# etna-main-ui.net
KiCad netlist of a schematic drawn in Altium Designer
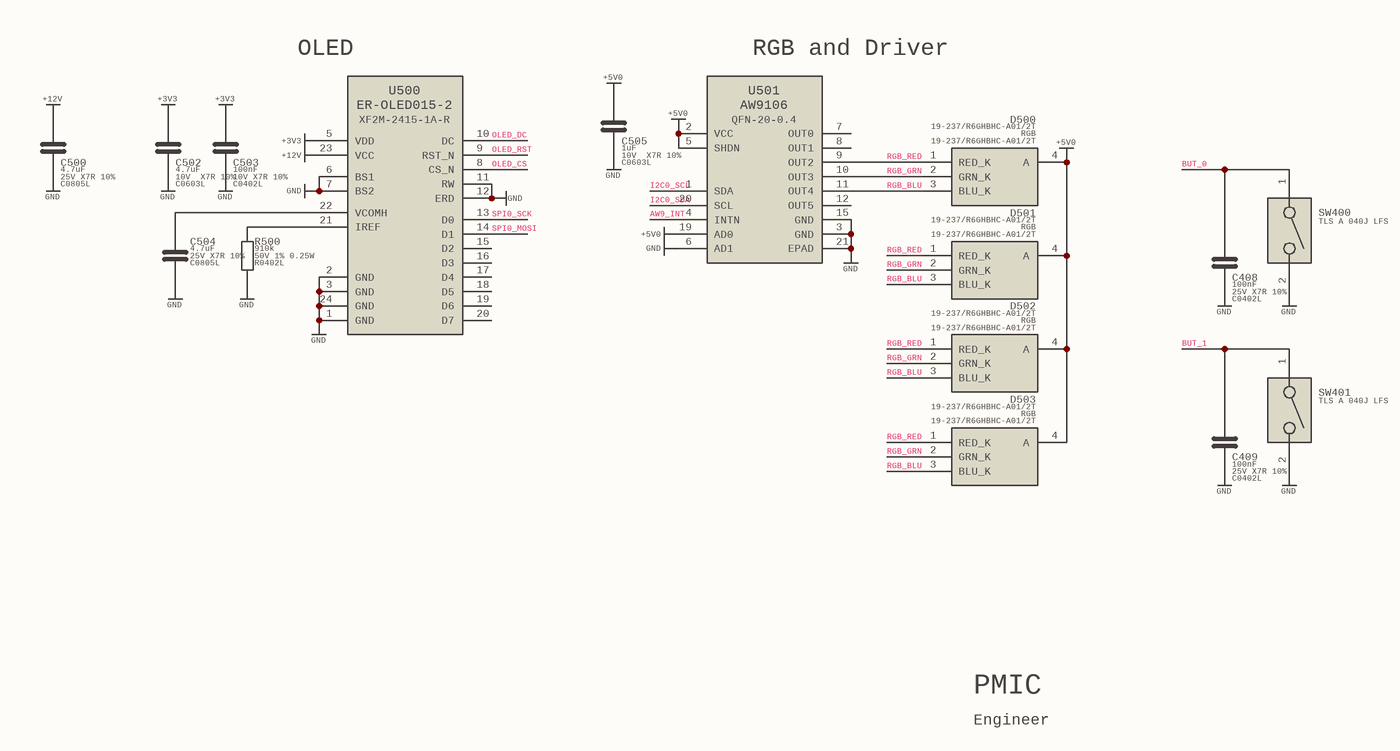
[diagram p0: etna-main-ui.SchDoc]

(export (version "E")
  (design (tool "Eeschema 10.0.6"))
  (components
    (comp (ref "C408")
      (value "100nF")
      (footprint "C0402L")
      (fields (field (name "SPECIFICATION") "25V X7R 10%"))
      (libsource (lib "passive") (part "CAPACITOR_NONPOL"))
    )
    (comp (ref "C409")
      (value "100nF")
      (footprint "C0402L")
      (fields (field (name "SPECIFICATION") "25V X7R 10%"))
      (libsource (lib "passive") (part "CAPACITOR_NONPOL"))
    )
    (comp (ref "C500")
      (value "4.7uF")
      (footprint "C0805L")
      (fields (field (name "SPECIFICATION") "25V X7R 10%"))
      (libsource (lib "passive") (part "CAPACITOR_NONPOL"))
    )
    (comp (ref "C502")
      (value "4.7uF")
      (footprint "C0603L")
      (fields (field (name "SPECIFICATION") "10V  X7R 10%"))
      (libsource (lib "passive") (part "CAPACITOR_NONPOL"))
    )
    (comp (ref "C503")
      (value "100nF")
      (footprint "C0402L")
      (fields (field (name "SPECIFICATION") "10V X7R 10%"))
      (libsource (lib "passive") (part "CAPACITOR_NONPOL"))
    )
    (comp (ref "C504")
      (value "4.7uF")
      (footprint "C0805L")
      (fields (field (name "SPECIFICATION") "25V X7R 10%"))
      (libsource (lib "passive") (part "CAPACITOR_NONPOL"))
    )
    (comp (ref "C505")
      (value "1uF")
      (footprint "C0603L")
      (fields (field (name "SPECIFICATION") "10V  X7R 10%"))
      (libsource (lib "passive") (part "CAPACITOR_NONPOL"))
    )
    (comp (ref "D500")
      (value "19-237/R6GHBHC-A01/2T")
      (footprint "19-237/R6GHBHC-A01/2T")
      (fields (field (name "SPECIFICATION") "RGB"))
      (libsource (lib "discreet") (part "19-237/R6GHBHC-A01/2T"))
    )
    (comp (ref "D501")
      (value "19-237/R6GHBHC-A01/2T")
      (footprint "19-237/R6GHBHC-A01/2T")
      (fields (field (name "SPECIFICATION") "RGB"))
      (libsource (lib "discreet") (part "19-237/R6GHBHC-A01/2T"))
    )
    (comp (ref "D502")
      (value "19-237/R6GHBHC-A01/2T")
      (footprint "19-237/R6GHBHC-A01/2T")
      (fields (field (name "SPECIFICATION") "RGB"))
      (libsource (lib "discreet") (part "19-237/R6GHBHC-A01/2T"))
    )
    (comp (ref "D503")
      (value "19-237/R6GHBHC-A01/2T")
      (footprint "19-237/R6GHBHC-A01/2T")
      (fields (field (name "SPECIFICATION") "RGB"))
      (libsource (lib "discreet") (part "19-237/R6GHBHC-A01/2T"))
    )
    (comp (ref "R500")
      (value "910k")
      (footprint "R0402L")
      (fields (field (name "SPECIFICATION") "50V 1% 0.25W"))
      (libsource (lib "passive") (part "RESISTOR"))
    )
    (comp (ref "SW400")
      (value "TLS A 040J LFS")
      (footprint "TLS A 040J LFS")
      (libsource (lib "legacy") (part "SWITCH"))
    )
    (comp (ref "SW401")
      (value "TLS A 040J LFS")
      (footprint "TLS A 040J LFS")
      (libsource (lib "legacy") (part "SWITCH"))
    )
    (comp (ref "U500")
      (value "ER-OLED015-2")
      (footprint "XF2M-2415-1A-R")
      (libsource (lib "ic") (part "ER-OLED015-2"))
    )
    (comp (ref "U501")
      (value "AW9106")
      (footprint "QFN-20-0.4")
      (fields (field (name "Comment") "AW9109"))
      (libsource (lib "ic") (part "AW9106"))
    )
  )
  (nets
    (net (code "1") (name "+3V3") (class "Default")
      (node (ref "C502") (pin "1") (pinfunction "1_1") (pintype "passive"))
      (node (ref "C503") (pin "1") (pinfunction "1_1") (pintype "passive"))
      (node (ref "U500") (pin "5") (pinfunction "VDD_5") (pintype "passive"))
    )
    (net (code "2") (name "+5V0") (class "Default")
      (node (ref "C505") (pin "1") (pinfunction "1_1") (pintype "passive"))
      (node (ref "D500") (pin "4") (pinfunction "A_4") (pintype "passive"))
      (node (ref "D501") (pin "4") (pinfunction "A_4") (pintype "passive"))
      (node (ref "D502") (pin "4") (pinfunction "A_4") (pintype "passive"))
      (node (ref "D503") (pin "4") (pinfunction "A_4") (pintype "passive"))
      (node (ref "U501") (pin "19") (pinfunction "AD0_19") (pintype "passive"))
      (node (ref "U501") (pin "2") (pinfunction "VCC_2") (pintype "passive"))
      (node (ref "U501") (pin "5") (pinfunction "SHDN_5") (pintype "passive"))
    )
    (net (code "3") (name "+12V") (class "Default")
      (node (ref "C500") (pin "1") (pinfunction "1_1") (pintype "passive"))
      (node (ref "U500") (pin "23") (pinfunction "VCC_23") (pintype "passive"))
    )
    (net (code "4") (name "/AW9_INT") (class "Default")
      (node (ref "U501") (pin "4") (pinfunction "INTN_4") (pintype "passive"))
    )
    (net (code "5") (name "/BUT_0") (class "Default")
      (node (ref "C408") (pin "1") (pinfunction "1_1") (pintype "passive"))
      (node (ref "SW400") (pin "1") (pinfunction "1_1") (pintype "passive"))
    )
    (net (code "6") (name "/BUT_1") (class "Default")
      (node (ref "C409") (pin "1") (pinfunction "1_1") (pintype "passive"))
      (node (ref "SW401") (pin "1") (pinfunction "1_1") (pintype "passive"))
    )
    (net (code "7") (name "/I2C0_SCL") (class "Default")
      (node (ref "U501") (pin "1") (pinfunction "SDA_1") (pintype "passive"))
    )
    (net (code "8") (name "/I2C0_SDA") (class "Default")
      (node (ref "U501") (pin "20") (pinfunction "SCL_20") (pintype "passive"))
    )
    (net (code "9") (name "/OLED_CS") (class "Default")
      (node (ref "U500") (pin "8") (pinfunction "CS_N_8") (pintype "passive"))
    )
    (net (code "10") (name "/OLED_DC") (class "Default")
      (node (ref "U500") (pin "10") (pinfunction "DC_10") (pintype "passive"))
    )
    (net (code "11") (name "/OLED_RST") (class "Default")
      (node (ref "U500") (pin "9") (pinfunction "RST_N_9") (pintype "passive"))
    )
    (net (code "12") (name "/RGB_BLU") (class "Default")
      (node (ref "D500") (pin "3") (pinfunction "BLU_K_3") (pintype "passive"))
      (node (ref "D501") (pin "3") (pinfunction "BLU_K_3") (pintype "passive"))
      (node (ref "D502") (pin "3") (pinfunction "BLU_K_3") (pintype "passive"))
      (node (ref "D503") (pin "3") (pinfunction "BLU_K_3") (pintype "passive"))
      (node (ref "U501") (pin "11") (pinfunction "OUT4_11") (pintype "passive"))
    )
    (net (code "13") (name "/RGB_GRN") (class "Default")
      (node (ref "D500") (pin "2") (pinfunction "GRN_K_2") (pintype "passive"))
      (node (ref "D501") (pin "2") (pinfunction "GRN_K_2") (pintype "passive"))
      (node (ref "D502") (pin "2") (pinfunction "GRN_K_2") (pintype "passive"))
      (node (ref "D503") (pin "2") (pinfunction "GRN_K_2") (pintype "passive"))
      (node (ref "U501") (pin "10") (pinfunction "OUT3_10") (pintype "passive"))
    )
    (net (code "14") (name "/RGB_RED") (class "Default")
      (node (ref "D500") (pin "1") (pinfunction "RED_K_1") (pintype "passive"))
      (node (ref "D501") (pin "1") (pinfunction "RED_K_1") (pintype "passive"))
      (node (ref "D502") (pin "1") (pinfunction "RED_K_1") (pintype "passive"))
      (node (ref "D503") (pin "1") (pinfunction "RED_K_1") (pintype "passive"))
      (node (ref "U501") (pin "9") (pinfunction "OUT2_9") (pintype "passive"))
    )
    (net (code "15") (name "/SPI0_MOSI") (class "Default")
      (node (ref "U500") (pin "14") (pinfunction "D1_14") (pintype "passive"))
    )
    (net (code "16") (name "/SPI0_SCK") (class "Default")
      (node (ref "U500") (pin "13") (pinfunction "D0_13") (pintype "passive"))
    )
    (net (code "17") (name "GND") (class "Default")
      (node (ref "C408") (pin "2") (pinfunction "2_2") (pintype "passive"))
      (node (ref "C409") (pin "2") (pinfunction "2_2") (pintype "passive"))
      (node (ref "C500") (pin "2") (pinfunction "2_2") (pintype "passive"))
      (node (ref "C502") (pin "2") (pinfunction "2_2") (pintype "passive"))
      (node (ref "C503") (pin "2") (pinfunction "2_2") (pintype "passive"))
      (node (ref "C504") (pin "2") (pinfunction "2_2") (pintype "passive"))
      (node (ref "C505") (pin "2") (pinfunction "2_2") (pintype "passive"))
      (node (ref "R500") (pin "2") (pinfunction "2_2") (pintype "passive"))
      (node (ref "SW400") (pin "2") (pinfunction "2_2") (pintype "passive"))
      (node (ref "SW401") (pin "2") (pinfunction "2_2") (pintype "passive"))
      (node (ref "U500") (pin "1") (pinfunction "GND_1") (pintype "passive"))
      (node (ref "U500") (pin "11") (pinfunction "RW_11") (pintype "passive"))
      (node (ref "U500") (pin "12") (pinfunction "ERD_12") (pintype "passive"))
      (node (ref "U500") (pin "2") (pinfunction "GND_2") (pintype "passive"))
      (node (ref "U500") (pin "24") (pinfunction "GND_24") (pintype "passive"))
      (node (ref "U500") (pin "3") (pinfunction "GND_3") (pintype "passive"))
      (node (ref "U500") (pin "6") (pinfunction "BS1_6") (pintype "passive"))
      (node (ref "U500") (pin "7") (pinfunction "BS2_7") (pintype "passive"))
      (node (ref "U501") (pin "15") (pinfunction "GND_15") (pintype "passive"))
      (node (ref "U501") (pin "21") (pinfunction "EPAD_21") (pintype "passive"))
      (node (ref "U501") (pin "3") (pinfunction "GND_3") (pintype "passive"))
      (node (ref "U501") (pin "6") (pinfunction "AD1_6") (pintype "passive"))
    )
    (net (code "18") (name "Net-(U500-IREF)") (class "Default")
      (node (ref "R500") (pin "1") (pinfunction "1_1") (pintype "passive"))
      (node (ref "U500") (pin "21") (pinfunction "IREF_21") (pintype "passive"))
    )
    (net (code "19") (name "Net-(U500-VCOMH)") (class "Default")
      (node (ref "C504") (pin "1") (pinfunction "1_1") (pintype "passive"))
      (node (ref "U500") (pin "22") (pinfunction "VCOMH_22") (pintype "passive"))
    )
    (net (code "20") (name "unconnected-(U500-D2-Pad15)") (class "Default")
      (node (ref "U500") (pin "15") (pinfunction "D2_15") (pintype "passive"))
    )
    (net (code "21") (name "unconnected-(U500-D3-Pad16)") (class "Default")
      (node (ref "U500") (pin "16") (pinfunction "D3_16") (pintype "passive"))
    )
    (net (code "22") (name "unconnected-(U500-D4-Pad17)") (class "Default")
      (node (ref "U500") (pin "17") (pinfunction "D4_17") (pintype "passive"))
    )
    (net (code "23") (name "unconnected-(U500-D5-Pad18)") (class "Default")
      (node (ref "U500") (pin "18") (pinfunction "D5_18") (pintype "passive"))
    )
    (net (code "24") (name "unconnected-(U500-D6-Pad19)") (class "Default")
      (node (ref "U500") (pin "19") (pinfunction "D6_19") (pintype "passive"))
    )
    (net (code "25") (name "unconnected-(U500-D7-Pad20)") (class "Default")
      (node (ref "U500") (pin "20") (pinfunction "D7_20") (pintype "passive"))
    )
    (net (code "26") (name "unconnected-(U500-N.C.-Pad44)") (class "Default")
      (node (ref "U500") (pin "44") (pinfunction "N.C._44") (pintype "passive"))
    )
    (net (code "27") (name "unconnected-(U501-N.C.-Pad44)") (class "Default")
      (node (ref "U501") (pin "44") (pinfunction "N.C._44") (pintype "passive"))
    )
    (net (code "28") (name "unconnected-(U501-OUT0-Pad7)") (class "Default")
      (node (ref "U501") (pin "7") (pinfunction "OUT0_7") (pintype "passive"))
    )
    (net (code "29") (name "unconnected-(U501-OUT1-Pad8)") (class "Default")
      (node (ref "U501") (pin "8") (pinfunction "OUT1_8") (pintype "passive"))
    )
    (net (code "30") (name "unconnected-(U501-OUT5-Pad12)") (class "Default")
      (node (ref "U501") (pin "12") (pinfunction "OUT5_12") (pintype "passive"))
    )
  )
)
